# main.net
KiCad netlist of a schematic drawn in EAGLE
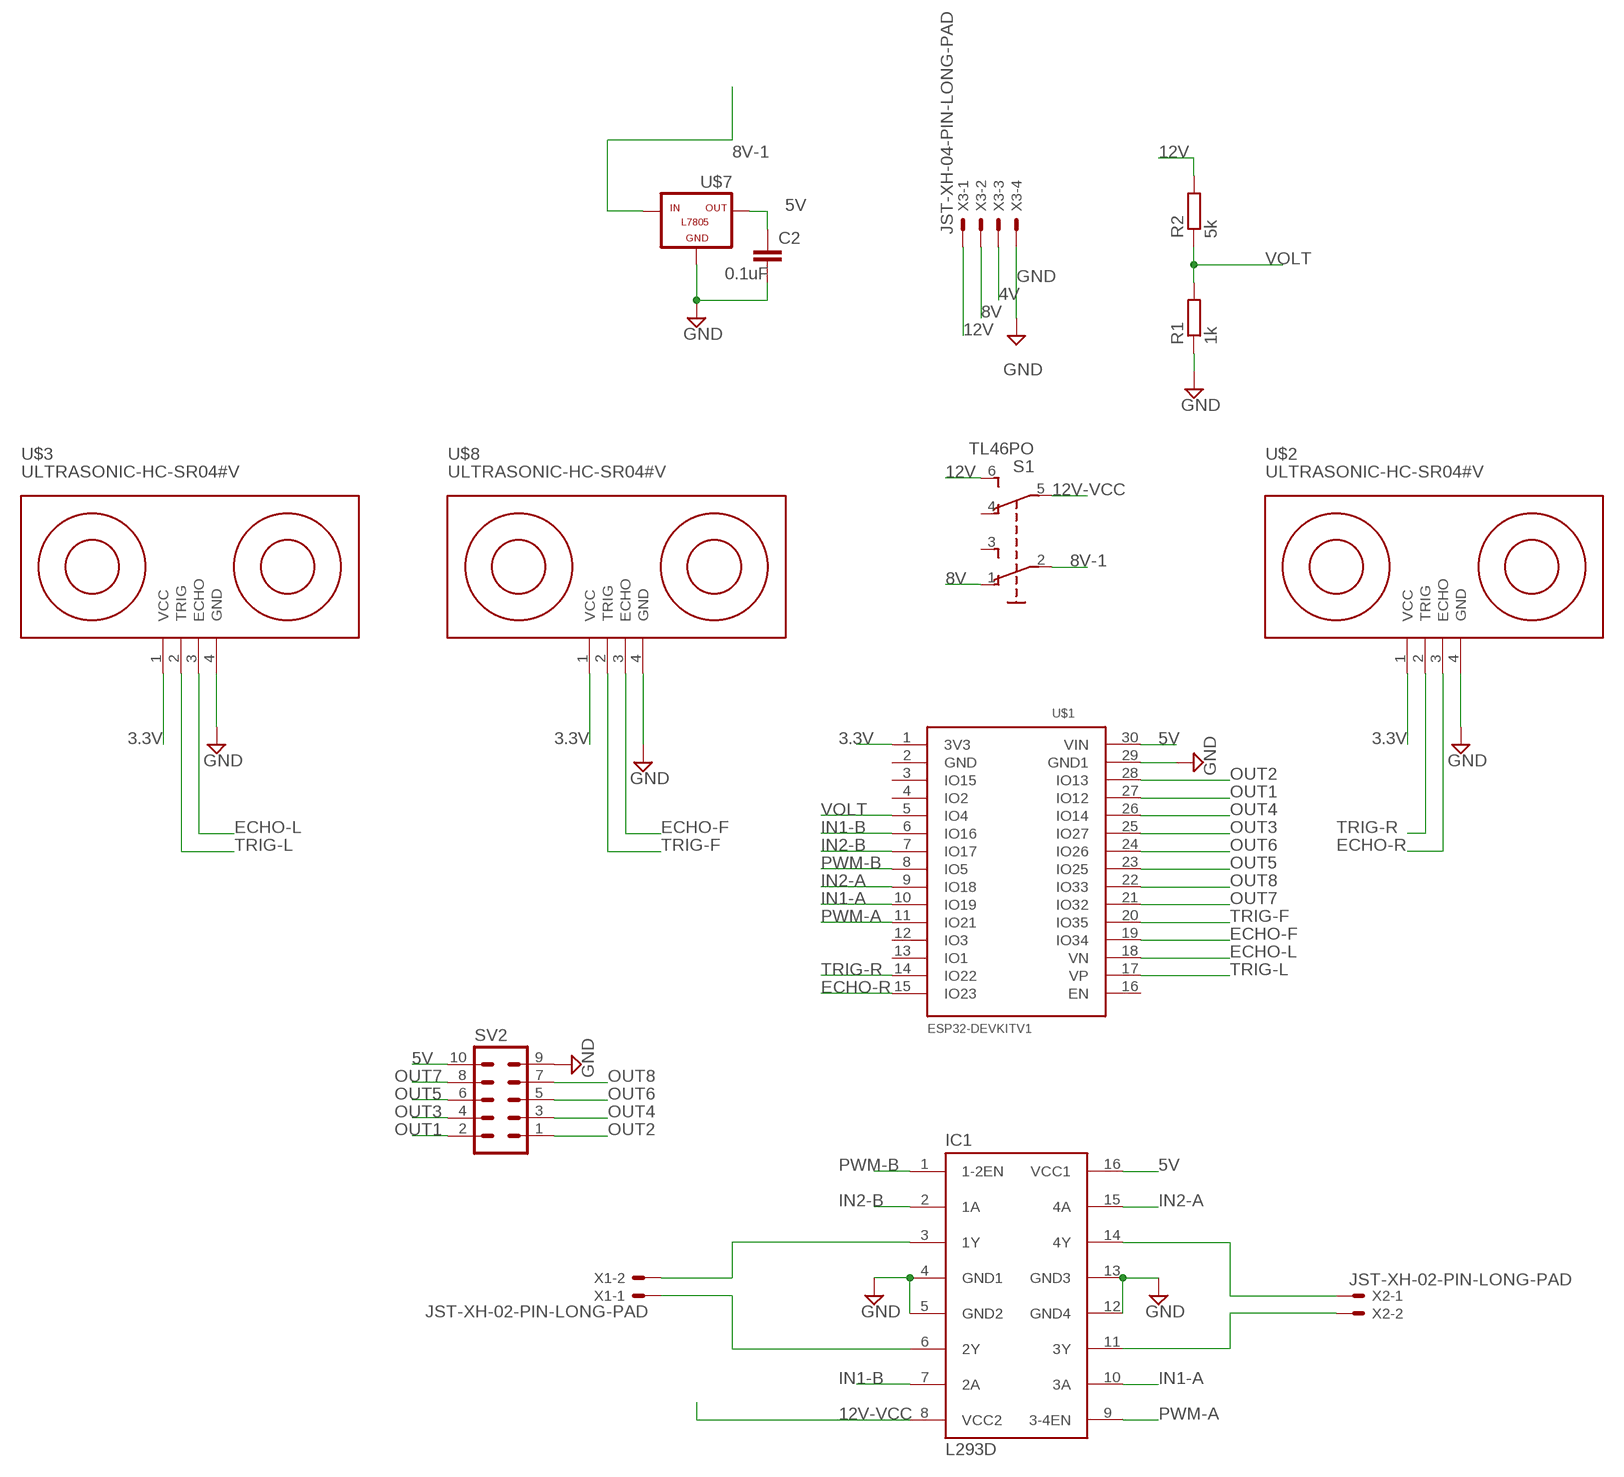
[diagram p0: schematic, sheet 1]

(export (version "E")
  (design (tool "Eeschema 10.0.6"))
  (components
    (comp (ref "C2")
      (value "0.1uF")
      (footprint "eagle-import:C2.5-3")
      (libsource (lib "eagle-import") (part "C2,5-3"))
    )
    (comp (ref "IC1")
      (value "L293D")
      (footprint "eagle-import:DIL16")
      (libsource (lib "eagle-import") (part "L293D"))
    )
    (comp (ref "R1")
      (value "1k")
      (footprint "eagle-import:0207_10")
      (libsource (lib "eagle-import") (part "R-EU_0207/10"))
    )
    (comp (ref "R2")
      (value "5k")
      (footprint "eagle-import:0207_10")
      (libsource (lib "eagle-import") (part "R-EU_0207/10"))
    )
    (comp (ref "S1")
      (value "TL46PO")
      (footprint "eagle-import:TL4XPO")
      (libsource (lib "eagle-import") (part "TL46PO"))
    )
    (comp (ref "SV2")
      (value "MA05-2")
      (footprint "eagle-import:MA05-2")
      (libsource (lib "eagle-import") (part "MA05-2"))
    )
    (comp (ref "U$1")
      (value "ESP32DEVKITV1")
      (footprint "eagle-import:ESP32-DEVKITV1")
      (libsource (lib "eagle-import") (part "ESP32DEVKITV1"))
    )
    (comp (ref "U$2")
      (value "ULTRASONIC-HC-SR04#V")
      (footprint "eagle-import:ULTRASONIC-HC-SR04#V")
      (libsource (lib "eagle-import") (part "ULTRASONIC-HC-SR04#V"))
    )
    (comp (ref "U$3")
      (value "ULTRASONIC-HC-SR04#V")
      (footprint "eagle-import:ULTRASONIC-HC-SR04#V")
      (libsource (lib "eagle-import") (part "ULTRASONIC-HC-SR04#V"))
    )
    (comp (ref "U$7")
      (value "-L7805")
      (footprint "eagle-import:L7805")
      (libsource (lib "eagle-import") (part "-L7805"))
    )
    (comp (ref "U$8")
      (value "ULTRASONIC-HC-SR04#V")
      (footprint "eagle-import:ULTRASONIC-HC-SR04#V")
      (libsource (lib "eagle-import") (part "ULTRASONIC-HC-SR04#V"))
    )
    (comp (ref "X1")
      (value "JST-XH-02-PIN-LONG-PAD")
      (footprint "eagle-import:JST-XH-02-PACKAGE-LONG-PAD")
      (libsource (lib "eagle-import") (part "JST-XH-02-PIN-LONG-PAD"))
    )
    (comp (ref "X2")
      (value "JST-XH-02-PIN-LONG-PAD")
      (footprint "eagle-import:JST-XH-02-PACKAGE-LONG-PAD")
      (libsource (lib "eagle-import") (part "JST-XH-02-PIN-LONG-PAD"))
    )
    (comp (ref "X3")
      (value "JST-XH-04-PIN-LONG-PAD")
      (footprint "eagle-import:JST-XH-04-PACKAGE-LONG-PAD")
      (libsource (lib "eagle-import") (part "JST-XH-04-PIN-LONG-PAD"))
    )
  )
  (nets
    (net (code "1") (name "/3.3V") (class "Default")
      (node (ref "U$1") (pin "1") (pinfunction "3V3_1") (pintype "bidirectional"))
      (node (ref "U$2") (pin "1") (pinfunction "VCC_1") (pintype "power_in"))
      (node (ref "U$3") (pin "1") (pinfunction "VCC_1") (pintype "power_in"))
      (node (ref "U$8") (pin "1") (pinfunction "VCC_1") (pintype "power_in"))
    )
    (net (code "2") (name "/4V") (class "Default")
      (node (ref "X3") (pin "3") (pinfunction "S_3") (pintype "passive"))
    )
    (net (code "3") (name "/5V") (class "Default")
      (node (ref "C2") (pin "1") (pinfunction "1_1") (pintype "passive"))
      (node (ref "IC1") (pin "16") (pinfunction "VCC1_16") (pintype "power_in"))
      (node (ref "SV2") (pin "10") (pinfunction "10_10") (pintype "passive"))
      (node (ref "U$1") (pin "30") (pinfunction "VIN_30") (pintype "bidirectional"))
      (node (ref "U$7") (pin "OUT") (pinfunction "OUT_OUT") (pintype "passive"))
    )
    (net (code "4") (name "/8V") (class "Default")
      (node (ref "S1") (pin "1") (pinfunction "O_1") (pintype "passive"))
      (node (ref "X3") (pin "2") (pinfunction "S_2") (pintype "passive"))
    )
    (net (code "5") (name "/8V-1") (class "Default")
      (node (ref "S1") (pin "2") (pinfunction "P_2") (pintype "passive"))
      (node (ref "U$7") (pin "IN") (pinfunction "IN_IN") (pintype "input"))
    )
    (net (code "6") (name "/12V") (class "Default")
      (node (ref "R2") (pin "2") (pinfunction "2_2") (pintype "passive"))
      (node (ref "S1") (pin "6") (pinfunction "S1_6") (pintype "passive"))
      (node (ref "X3") (pin "1") (pinfunction "S_1") (pintype "passive"))
    )
    (net (code "7") (name "/12V-VCC") (class "Default")
      (node (ref "IC1") (pin "8") (pinfunction "VCC2_8") (pintype "power_in"))
      (node (ref "S1") (pin "5") (pinfunction "P1_5") (pintype "passive"))
    )
    (net (code "8") (name "/ECHO-F") (class "Default")
      (node (ref "U$1") (pin "19") (pinfunction "IO34_19") (pintype "bidirectional"))
      (node (ref "U$8") (pin "3") (pinfunction "ECHO_3") (pintype "output"))
    )
    (net (code "9") (name "/ECHO-L") (class "Default")
      (node (ref "U$1") (pin "18") (pinfunction "VN_18") (pintype "bidirectional"))
      (node (ref "U$3") (pin "3") (pinfunction "ECHO_3") (pintype "output"))
    )
    (net (code "10") (name "/ECHO-R") (class "Default")
      (node (ref "U$1") (pin "15") (pinfunction "IO23_15") (pintype "bidirectional"))
      (node (ref "U$2") (pin "3") (pinfunction "ECHO_3") (pintype "output"))
    )
    (net (code "11") (name "/IN1-A") (class "Default")
      (node (ref "IC1") (pin "10") (pinfunction "3A_10") (pintype "input"))
      (node (ref "U$1") (pin "10") (pinfunction "IO19_10") (pintype "bidirectional"))
    )
    (net (code "12") (name "/IN1-B") (class "Default")
      (node (ref "IC1") (pin "7") (pinfunction "2A_7") (pintype "input"))
      (node (ref "U$1") (pin "6") (pinfunction "IO16_6") (pintype "bidirectional"))
    )
    (net (code "13") (name "/IN2-A") (class "Default")
      (node (ref "IC1") (pin "15") (pinfunction "4A_15") (pintype "input"))
      (node (ref "U$1") (pin "9") (pinfunction "IO18_9") (pintype "bidirectional"))
    )
    (net (code "14") (name "/IN2-B") (class "Default")
      (node (ref "IC1") (pin "2") (pinfunction "1A_2") (pintype "input"))
      (node (ref "U$1") (pin "7") (pinfunction "IO17_7") (pintype "bidirectional"))
    )
    (net (code "15") (name "/OUT1") (class "Default")
      (node (ref "SV2") (pin "2") (pinfunction "2_2") (pintype "passive"))
      (node (ref "U$1") (pin "27") (pinfunction "IO12_27") (pintype "bidirectional"))
    )
    (net (code "16") (name "/OUT2") (class "Default")
      (node (ref "SV2") (pin "1") (pinfunction "1_1") (pintype "passive"))
      (node (ref "U$1") (pin "28") (pinfunction "IO13_28") (pintype "bidirectional"))
    )
    (net (code "17") (name "/OUT3") (class "Default")
      (node (ref "SV2") (pin "4") (pinfunction "4_4") (pintype "passive"))
      (node (ref "U$1") (pin "25") (pinfunction "IO27_25") (pintype "bidirectional"))
    )
    (net (code "18") (name "/OUT4") (class "Default")
      (node (ref "SV2") (pin "3") (pinfunction "3_3") (pintype "passive"))
      (node (ref "U$1") (pin "26") (pinfunction "IO14_26") (pintype "bidirectional"))
    )
    (net (code "19") (name "/OUT5") (class "Default")
      (node (ref "SV2") (pin "6") (pinfunction "6_6") (pintype "passive"))
      (node (ref "U$1") (pin "23") (pinfunction "IO25_23") (pintype "bidirectional"))
    )
    (net (code "20") (name "/OUT6") (class "Default")
      (node (ref "SV2") (pin "5") (pinfunction "5_5") (pintype "passive"))
      (node (ref "U$1") (pin "24") (pinfunction "IO26_24") (pintype "bidirectional"))
    )
    (net (code "21") (name "/OUT7") (class "Default")
      (node (ref "SV2") (pin "8") (pinfunction "8_8") (pintype "passive"))
      (node (ref "U$1") (pin "21") (pinfunction "IO32_21") (pintype "bidirectional"))
    )
    (net (code "22") (name "/OUT8") (class "Default")
      (node (ref "SV2") (pin "7") (pinfunction "7_7") (pintype "passive"))
      (node (ref "U$1") (pin "22") (pinfunction "IO33_22") (pintype "bidirectional"))
    )
    (net (code "23") (name "/PWM-A") (class "Default")
      (node (ref "IC1") (pin "9") (pinfunction "3-4EN_9") (pintype "input"))
      (node (ref "U$1") (pin "11") (pinfunction "IO21_11") (pintype "bidirectional"))
    )
    (net (code "24") (name "/PWM-B") (class "Default")
      (node (ref "IC1") (pin "1") (pinfunction "1-2EN_1") (pintype "input"))
      (node (ref "U$1") (pin "8") (pinfunction "IO5_8") (pintype "bidirectional"))
    )
    (net (code "25") (name "/TRIG-F") (class "Default")
      (node (ref "U$1") (pin "20") (pinfunction "IO35_20") (pintype "bidirectional"))
      (node (ref "U$8") (pin "2") (pinfunction "TRIG_2") (pintype "input"))
    )
    (net (code "26") (name "/TRIG-L") (class "Default")
      (node (ref "U$1") (pin "17") (pinfunction "VP_17") (pintype "bidirectional"))
      (node (ref "U$3") (pin "2") (pinfunction "TRIG_2") (pintype "input"))
    )
    (net (code "27") (name "/TRIG-R") (class "Default")
      (node (ref "U$1") (pin "14") (pinfunction "IO22_14") (pintype "bidirectional"))
      (node (ref "U$2") (pin "2") (pinfunction "TRIG_2") (pintype "input"))
    )
    (net (code "28") (name "/VOLT") (class "Default")
      (node (ref "R1") (pin "2") (pinfunction "2_2") (pintype "passive"))
      (node (ref "R2") (pin "1") (pinfunction "1_1") (pintype "passive"))
      (node (ref "U$1") (pin "5") (pinfunction "IO4_5") (pintype "bidirectional"))
    )
    (net (code "29") (name "GND") (class "Default")
      (node (ref "C2") (pin "2") (pinfunction "2_2") (pintype "passive"))
      (node (ref "IC1") (pin "12") (pinfunction "GND4_12") (pintype "power_in"))
      (node (ref "IC1") (pin "13") (pinfunction "GND3_13") (pintype "power_in"))
      (node (ref "IC1") (pin "4") (pinfunction "GND1_4") (pintype "power_in"))
      (node (ref "IC1") (pin "5") (pinfunction "GND2_5") (pintype "power_in"))
      (node (ref "R1") (pin "1") (pinfunction "1_1") (pintype "passive"))
      (node (ref "SV2") (pin "9") (pinfunction "9_9") (pintype "passive"))
      (node (ref "U$1") (pin "29") (pinfunction "GND1_29") (pintype "bidirectional"))
      (node (ref "U$2") (pin "4") (pinfunction "GND_4") (pintype "power_in"))
      (node (ref "U$3") (pin "4") (pinfunction "GND_4") (pintype "power_in"))
      (node (ref "U$7") (pin "GND") (pinfunction "GND_GND") (pintype "input"))
      (node (ref "U$8") (pin "4") (pinfunction "GND_4") (pintype "power_in"))
      (node (ref "X3") (pin "4") (pinfunction "S_4") (pintype "passive"))
    )
    (net (code "30") (name "Net-(IC1-1Y)") (class "Default")
      (node (ref "IC1") (pin "3") (pinfunction "1Y_3") (pintype "output"))
      (node (ref "X1") (pin "2") (pinfunction "S_2") (pintype "passive"))
    )
    (net (code "31") (name "Net-(IC1-2Y)") (class "Default")
      (node (ref "IC1") (pin "6") (pinfunction "2Y_6") (pintype "output"))
      (node (ref "X1") (pin "1") (pinfunction "S_1") (pintype "passive"))
    )
    (net (code "32") (name "Net-(IC1-3Y)") (class "Default")
      (node (ref "IC1") (pin "11") (pinfunction "3Y_11") (pintype "output"))
      (node (ref "X2") (pin "2") (pinfunction "S_2") (pintype "passive"))
    )
    (net (code "33") (name "Net-(IC1-4Y)") (class "Default")
      (node (ref "IC1") (pin "14") (pinfunction "4Y_14") (pintype "output"))
      (node (ref "X2") (pin "1") (pinfunction "S_1") (pintype "passive"))
    )
    (net (code "34") (name "unconnected-(S1-O1-Pad4)") (class "Default")
      (node (ref "S1") (pin "4") (pinfunction "O1_4") (pintype "passive"))
    )
    (net (code "35") (name "unconnected-(S1-S-Pad3)") (class "Default")
      (node (ref "S1") (pin "3") (pinfunction "S_3") (pintype "passive"))
    )
    (net (code "36") (name "unconnected-(U$1-EN-Pad16)") (class "Default")
      (node (ref "U$1") (pin "16") (pinfunction "EN_16") (pintype "bidirectional"))
    )
    (net (code "37") (name "unconnected-(U$1-GND-Pad2)") (class "Default")
      (node (ref "U$1") (pin "2") (pinfunction "GND_2") (pintype "bidirectional"))
    )
    (net (code "38") (name "unconnected-(U$1-IO1-Pad13)") (class "Default")
      (node (ref "U$1") (pin "13") (pinfunction "IO1_13") (pintype "bidirectional"))
    )
    (net (code "39") (name "unconnected-(U$1-IO2-Pad4)") (class "Default")
      (node (ref "U$1") (pin "4") (pinfunction "IO2_4") (pintype "bidirectional"))
    )
    (net (code "40") (name "unconnected-(U$1-IO3-Pad12)") (class "Default")
      (node (ref "U$1") (pin "12") (pinfunction "IO3_12") (pintype "bidirectional"))
    )
    (net (code "41") (name "unconnected-(U$1-IO15-Pad3)") (class "Default")
      (node (ref "U$1") (pin "3") (pinfunction "IO15_3") (pintype "bidirectional"))
    )
  )
)
